# MotoDriver.net
KiCad netlist of a schematic drawn in EAGLE
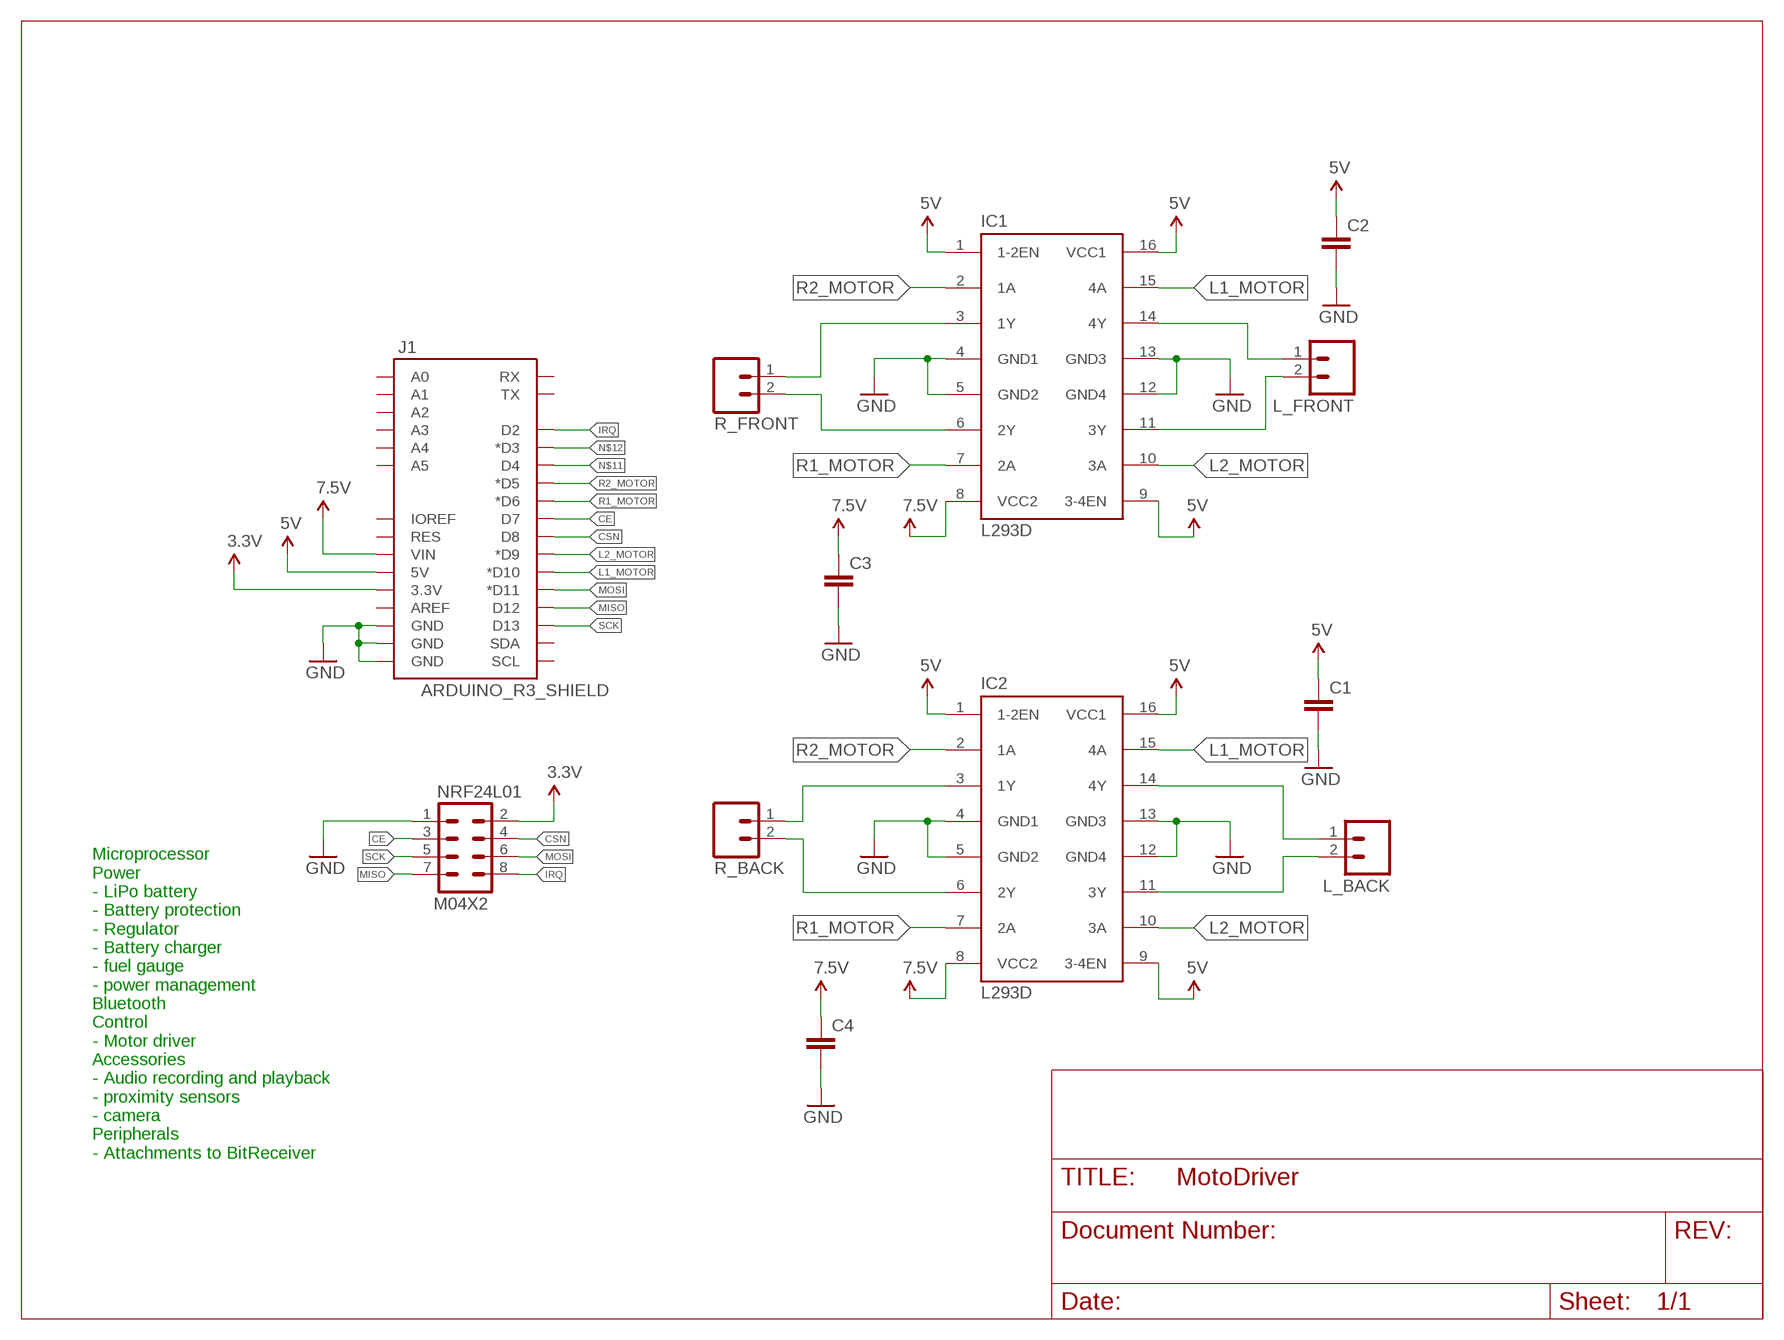
[diagram p0: schematic, sheet 1]

(export (version "E")
  (design (tool "Eeschema 10.0.6"))
  (components
    (comp (ref "C1")
      (value "C-EU050-024X044")
      (footprint "eagle-import:C050-024X044")
      (libsource (lib "eagle-import") (part "C-EU050-024X044"))
    )
    (comp (ref "C2")
      (value "C-EU050-024X044")
      (footprint "eagle-import:C050-024X044")
      (libsource (lib "eagle-import") (part "C-EU050-024X044"))
    )
    (comp (ref "C3")
      (value "C-EU050-024X044")
      (footprint "eagle-import:C050-024X044")
      (libsource (lib "eagle-import") (part "C-EU050-024X044"))
    )
    (comp (ref "C4")
      (value "C-EU050-024X044")
      (footprint "eagle-import:C050-024X044")
      (libsource (lib "eagle-import") (part "C-EU050-024X044"))
    )
    (comp (ref "IC1")
      (value "L293D")
      (footprint "eagle-import:DIL16")
      (libsource (lib "eagle-import") (part "L293D"))
    )
    (comp (ref "IC2")
      (value "L293D")
      (footprint "eagle-import:DIL16")
      (libsource (lib "eagle-import") (part "L293D"))
    )
    (comp (ref "J1")
      (value "ARDUINO_R3_SHIELD")
      (footprint "eagle-import:UNO_R3_SHIELD")
      (libsource (lib "eagle-import") (part "ARDUINO_R3_SHIELD"))
    )
    (comp (ref "L_BACK")
      (value "M021X02_NO_SILK")
      (footprint "eagle-import:1X02_NO_SILK")
      (libsource (lib "eagle-import") (part "M021X02_NO_SILK"))
    )
    (comp (ref "L_FRONT")
      (value "M021X02_NO_SILK")
      (footprint "eagle-import:1X02_NO_SILK")
      (libsource (lib "eagle-import") (part "M021X02_NO_SILK"))
    )
    (comp (ref "NRF24L01")
      (value "M04X2")
      (footprint "eagle-import:2X4")
      (libsource (lib "eagle-import") (part "M04X2"))
    )
    (comp (ref "R_BACK")
      (value "M021X02_NO_SILK")
      (footprint "eagle-import:1X02_NO_SILK")
      (libsource (lib "eagle-import") (part "M021X02_NO_SILK"))
    )
    (comp (ref "R_FRONT")
      (value "M021X02_NO_SILK")
      (footprint "eagle-import:1X02_NO_SILK")
      (libsource (lib "eagle-import") (part "M021X02_NO_SILK"))
    )
  )
  (nets
    (net (code "1") (name "3.3V") (class "Default")
      (node (ref "J1") (pin "3.3V") (pinfunction "3.3V_3.3V") (pintype "bidirectional"))
      (node (ref "NRF24L01") (pin "2") (pinfunction "2_2") (pintype "passive"))
    )
    (net (code "2") (name "5V") (class "Default")
      (node (ref "C1") (pin "1") (pinfunction "1_1") (pintype "passive"))
      (node (ref "C2") (pin "1") (pinfunction "1_1") (pintype "passive"))
      (node (ref "IC1") (pin "1") (pinfunction "1-2EN_1") (pintype "input"))
      (node (ref "IC1") (pin "16") (pinfunction "VCC1_16") (pintype "power_in"))
      (node (ref "IC1") (pin "9") (pinfunction "3-4EN_9") (pintype "input"))
      (node (ref "IC2") (pin "1") (pinfunction "1-2EN_1") (pintype "input"))
      (node (ref "IC2") (pin "16") (pinfunction "VCC1_16") (pintype "power_in"))
      (node (ref "IC2") (pin "9") (pinfunction "3-4EN_9") (pintype "input"))
      (node (ref "J1") (pin "5V") (pinfunction "5V_5V") (pintype "bidirectional"))
    )
    (net (code "3") (name "7.5V") (class "Default")
      (node (ref "C3") (pin "1") (pinfunction "1_1") (pintype "passive"))
      (node (ref "C4") (pin "1") (pinfunction "1_1") (pintype "passive"))
      (node (ref "IC1") (pin "8") (pinfunction "VCC2_8") (pintype "power_in"))
      (node (ref "IC2") (pin "8") (pinfunction "VCC2_8") (pintype "power_in"))
      (node (ref "J1") (pin "VIN") (pinfunction "VIN_VIN") (pintype "bidirectional"))
    )
    (net (code "4") (name "CE") (class "Default")
      (node (ref "J1") (pin "D7") (pinfunction "D7_D7") (pintype "bidirectional"))
      (node (ref "NRF24L01") (pin "3") (pinfunction "3_3") (pintype "passive"))
    )
    (net (code "5") (name "CSN") (class "Default")
      (node (ref "J1") (pin "D8") (pinfunction "D8_D8") (pintype "bidirectional"))
      (node (ref "NRF24L01") (pin "4") (pinfunction "4_4") (pintype "passive"))
    )
    (net (code "6") (name "GND") (class "Default")
      (node (ref "C1") (pin "2") (pinfunction "2_2") (pintype "passive"))
      (node (ref "C2") (pin "2") (pinfunction "2_2") (pintype "passive"))
      (node (ref "C3") (pin "2") (pinfunction "2_2") (pintype "passive"))
      (node (ref "C4") (pin "2") (pinfunction "2_2") (pintype "passive"))
      (node (ref "IC1") (pin "12") (pinfunction "GND4_12") (pintype "power_in"))
      (node (ref "IC1") (pin "13") (pinfunction "GND3_13") (pintype "power_in"))
      (node (ref "IC1") (pin "4") (pinfunction "GND1_4") (pintype "power_in"))
      (node (ref "IC1") (pin "5") (pinfunction "GND2_5") (pintype "power_in"))
      (node (ref "IC2") (pin "12") (pinfunction "GND4_12") (pintype "power_in"))
      (node (ref "IC2") (pin "13") (pinfunction "GND3_13") (pintype "power_in"))
      (node (ref "IC2") (pin "4") (pinfunction "GND1_4") (pintype "power_in"))
      (node (ref "IC2") (pin "5") (pinfunction "GND2_5") (pintype "power_in"))
      (node (ref "J1") (pin "GND@0") (pinfunction "GND_GND@0") (pintype "bidirectional"))
      (node (ref "J1") (pin "GND@1") (pinfunction "GND_GND@1") (pintype "bidirectional"))
      (node (ref "J1") (pin "GND@2") (pinfunction "GND_GND@2") (pintype "bidirectional"))
      (node (ref "NRF24L01") (pin "1") (pinfunction "1_1") (pintype "passive"))
    )
    (net (code "7") (name "IRQ") (class "Default")
      (node (ref "J1") (pin "D2") (pinfunction "D2_D2") (pintype "bidirectional"))
      (node (ref "NRF24L01") (pin "8") (pinfunction "8_8") (pintype "passive"))
    )
    (net (code "8") (name "L1_MOTOR") (class "Default")
      (node (ref "IC1") (pin "15") (pinfunction "4A_15") (pintype "input"))
      (node (ref "IC2") (pin "15") (pinfunction "4A_15") (pintype "input"))
      (node (ref "J1") (pin "D10") (pinfunction "*D10_D10") (pintype "bidirectional"))
    )
    (net (code "9") (name "L2_MOTOR") (class "Default")
      (node (ref "IC1") (pin "10") (pinfunction "3A_10") (pintype "input"))
      (node (ref "IC2") (pin "10") (pinfunction "3A_10") (pintype "input"))
      (node (ref "J1") (pin "D9") (pinfunction "*D9_D9") (pintype "bidirectional"))
    )
    (net (code "10") (name "MISO") (class "Default")
      (node (ref "J1") (pin "D12") (pinfunction "D12_D12") (pintype "bidirectional"))
      (node (ref "NRF24L01") (pin "7") (pinfunction "7_7") (pintype "passive"))
    )
    (net (code "11") (name "MOSI") (class "Default")
      (node (ref "J1") (pin "D11") (pinfunction "*D11_D11") (pintype "bidirectional"))
      (node (ref "NRF24L01") (pin "6") (pinfunction "6_6") (pintype "passive"))
    )
    (net (code "12") (name "N$11") (class "Default")
      (node (ref "J1") (pin "D4") (pinfunction "D4_D4") (pintype "bidirectional"))
    )
    (net (code "13") (name "N$12") (class "Default")
      (node (ref "J1") (pin "D3") (pinfunction "*D3_D3") (pintype "bidirectional"))
    )
    (net (code "14") (name "Net-(IC1-1Y)") (class "Default")
      (node (ref "IC1") (pin "3") (pinfunction "1Y_3") (pintype "output"))
      (node (ref "R_FRONT") (pin "1") (pinfunction "1_1") (pintype "passive"))
    )
    (net (code "15") (name "Net-(IC1-2Y)") (class "Default")
      (node (ref "IC1") (pin "6") (pinfunction "2Y_6") (pintype "output"))
      (node (ref "R_FRONT") (pin "2") (pinfunction "2_2") (pintype "passive"))
    )
    (net (code "16") (name "Net-(IC1-3Y)") (class "Default")
      (node (ref "IC1") (pin "11") (pinfunction "3Y_11") (pintype "output"))
      (node (ref "L_FRONT") (pin "2") (pinfunction "2_2") (pintype "passive"))
    )
    (net (code "17") (name "Net-(IC1-4Y)") (class "Default")
      (node (ref "IC1") (pin "14") (pinfunction "4Y_14") (pintype "output"))
      (node (ref "L_FRONT") (pin "1") (pinfunction "1_1") (pintype "passive"))
    )
    (net (code "18") (name "Net-(IC2-1Y)") (class "Default")
      (node (ref "IC2") (pin "3") (pinfunction "1Y_3") (pintype "output"))
      (node (ref "R_BACK") (pin "1") (pinfunction "1_1") (pintype "passive"))
    )
    (net (code "19") (name "Net-(IC2-2Y)") (class "Default")
      (node (ref "IC2") (pin "6") (pinfunction "2Y_6") (pintype "output"))
      (node (ref "R_BACK") (pin "2") (pinfunction "2_2") (pintype "passive"))
    )
    (net (code "20") (name "Net-(IC2-3Y)") (class "Default")
      (node (ref "IC2") (pin "11") (pinfunction "3Y_11") (pintype "output"))
      (node (ref "L_BACK") (pin "2") (pinfunction "2_2") (pintype "passive"))
    )
    (net (code "21") (name "Net-(IC2-4Y)") (class "Default")
      (node (ref "IC2") (pin "14") (pinfunction "4Y_14") (pintype "output"))
      (node (ref "L_BACK") (pin "1") (pinfunction "1_1") (pintype "passive"))
    )
    (net (code "22") (name "R1_MOTOR") (class "Default")
      (node (ref "IC1") (pin "7") (pinfunction "2A_7") (pintype "input"))
      (node (ref "IC2") (pin "7") (pinfunction "2A_7") (pintype "input"))
      (node (ref "J1") (pin "D6") (pinfunction "*D6_D6") (pintype "bidirectional"))
    )
    (net (code "23") (name "R2_MOTOR") (class "Default")
      (node (ref "IC1") (pin "2") (pinfunction "1A_2") (pintype "input"))
      (node (ref "IC2") (pin "2") (pinfunction "1A_2") (pintype "input"))
      (node (ref "J1") (pin "D5") (pinfunction "*D5_D5") (pintype "bidirectional"))
    )
    (net (code "24") (name "SCK") (class "Default")
      (node (ref "J1") (pin "D13") (pinfunction "D13_D13") (pintype "bidirectional"))
      (node (ref "NRF24L01") (pin "5") (pinfunction "5_5") (pintype "passive"))
    )
    (net (code "25") (name "unconnected-(J1-PadA0)") (class "Default")
      (node (ref "J1") (pin "A0") (pinfunction "A0_A0") (pintype "bidirectional"))
    )
    (net (code "26") (name "unconnected-(J1-PadA1)") (class "Default")
      (node (ref "J1") (pin "A1") (pinfunction "A1_A1") (pintype "bidirectional"))
    )
    (net (code "27") (name "unconnected-(J1-PadA2)") (class "Default")
      (node (ref "J1") (pin "A2") (pinfunction "A2_A2") (pintype "bidirectional"))
    )
    (net (code "28") (name "unconnected-(J1-PadA3)") (class "Default")
      (node (ref "J1") (pin "A3") (pinfunction "A3_A3") (pintype "bidirectional"))
    )
    (net (code "29") (name "unconnected-(J1-PadA4)") (class "Default")
      (node (ref "J1") (pin "A4") (pinfunction "A4_A4") (pintype "bidirectional"))
    )
    (net (code "30") (name "unconnected-(J1-PadA5)") (class "Default")
      (node (ref "J1") (pin "A5") (pinfunction "A5_A5") (pintype "bidirectional"))
    )
    (net (code "31") (name "unconnected-(J1-PadAREF)") (class "Default")
      (node (ref "J1") (pin "AREF") (pinfunction "AREF_AREF") (pintype "bidirectional"))
    )
    (net (code "32") (name "unconnected-(J1-PadIOREF)") (class "Default")
      (node (ref "J1") (pin "IOREF") (pinfunction "IOREF_IOREF") (pintype "bidirectional"))
    )
    (net (code "33") (name "unconnected-(J1-PadRES)") (class "Default")
      (node (ref "J1") (pin "RES") (pinfunction "RES_RES") (pintype "bidirectional"))
    )
    (net (code "34") (name "unconnected-(J1-PadRX)") (class "Default")
      (node (ref "J1") (pin "RX") (pinfunction "RX_RX") (pintype "bidirectional"))
    )
    (net (code "35") (name "unconnected-(J1-PadSCL)") (class "Default")
      (node (ref "J1") (pin "SCL") (pinfunction "SCL_SCL") (pintype "bidirectional"))
    )
    (net (code "36") (name "unconnected-(J1-PadSDA)") (class "Default")
      (node (ref "J1") (pin "SDA") (pinfunction "SDA_SDA") (pintype "bidirectional"))
    )
    (net (code "37") (name "unconnected-(J1-PadTX)") (class "Default")
      (node (ref "J1") (pin "TX") (pinfunction "TX_TX") (pintype "bidirectional"))
    )
  )
)
